# Sheet1.net
KiCad netlist of a schematic drawn in Altium Designer
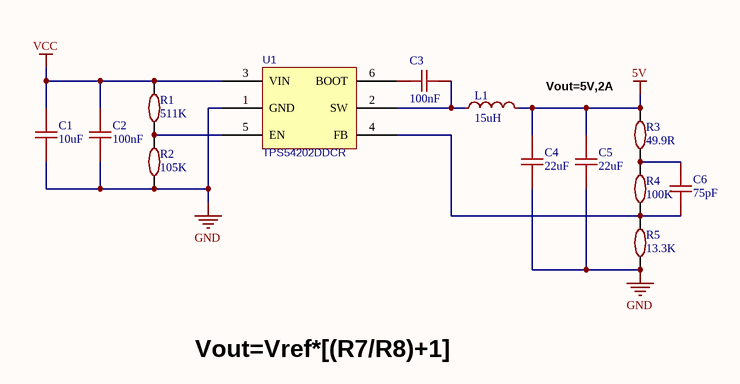
[diagram p0: Sheet1.SchDoc]

(export (version "E")
  (design (tool "Eeschema 10.0.6"))
  (components
    (comp (ref "C1")
      (value "10uF")
      (footprint "C_0603")
      (description "4.7nf-4.7uf")
      (libsource (lib "RCLD") (part "C_0603"))
    )
    (comp (ref "C2")
      (value "100nF")
      (footprint "C_0603")
      (description "4.7nf-4.7uf")
      (libsource (lib "RCLD") (part "C_0603"))
    )
    (comp (ref "C3")
      (value "100nF")
      (footprint "C_0603")
      (description "4.7nf-4.7uf")
      (libsource (lib "RCLD") (part "C_0603"))
    )
    (comp (ref "C4")
      (value "22uF")
      (footprint "C_0603")
      (description "4.7nf-4.7uf")
      (libsource (lib "RCLD") (part "C_0603"))
    )
    (comp (ref "C5")
      (value "22uF")
      (footprint "C_0603")
      (description "4.7nf-4.7uf")
      (libsource (lib "RCLD") (part "C_0603"))
    )
    (comp (ref "C6")
      (value "75pF")
      (footprint "C_0603")
      (description "4.7nf-4.7uf")
      (libsource (lib "RCLD") (part "C_0603"))
    )
    (comp (ref "L1")
      (value "15uH")
      (footprint "L-SMD-0630")
      (description "一体成型电感")
      (libsource (lib "RCLD") (part "L_33uH_0603"))
    )
    (comp (ref "R1") (value "511K") (footprint "R_0603") (libsource (lib "RCLD") (part "R_0603")))
    (comp (ref "R2") (value "105K") (footprint "R_0603") (libsource (lib "RCLD") (part "R_0603")))
    (comp (ref "R3") (value "49.9R") (footprint "R_0603") (libsource (lib "RCLD") (part "R_0603")))
    (comp (ref "R4") (value "100K") (footprint "R_0603") (libsource (lib "RCLD") (part "R_0603")))
    (comp (ref "R5") (value "13.3K") (footprint "R_0603") (libsource (lib "RCLD") (part "R_0603")))
    (comp (ref "U1")
      (value "TPS54202DDCR")
      (footprint "SOT23-6L")
      (fields (field (name "BOM_SUPPLIER PART") "C191884") (field (name "CONTRIBUTOR") "LCSC"))
      (libsource (lib "电源管理IC") (part "TPS54202DDCR"))
    )
  )
  (nets
    (net (code "1") (name "5V") (class "Default")
      (node (ref "C4") (pin "2") (pinfunction "2_2") (pintype "passive"))
      (node (ref "C5") (pin "2") (pinfunction "2_2") (pintype "passive"))
      (node (ref "L1") (pin "2") (pinfunction "2_2") (pintype "passive"))
      (node (ref "R3") (pin "2") (pinfunction "2_2") (pintype "passive"))
    )
    (net (code "2") (name "GND") (class "Default")
      (node (ref "C1") (pin "1") (pinfunction "1_1") (pintype "passive"))
      (node (ref "C2") (pin "1") (pinfunction "1_1") (pintype "passive"))
      (node (ref "C4") (pin "1") (pinfunction "1_1") (pintype "passive"))
      (node (ref "C5") (pin "1") (pinfunction "1_1") (pintype "passive"))
      (node (ref "R2") (pin "1") (pinfunction "1_1") (pintype "passive"))
      (node (ref "R5") (pin "1") (pinfunction "1_1") (pintype "passive"))
      (node (ref "U1") (pin "1") (pinfunction "GND_1") (pintype "passive"))
    )
    (net (code "3") (name "Net-(C6-Pad2)") (class "Default")
      (node (ref "C6") (pin "2") (pinfunction "2_2") (pintype "passive"))
      (node (ref "R3") (pin "1") (pinfunction "1_1") (pintype "passive"))
      (node (ref "R4") (pin "2") (pinfunction "2_2") (pintype "passive"))
    )
    (net (code "4") (name "Net-(U1-BOOT)") (class "Default")
      (node (ref "C3") (pin "2") (pinfunction "2_2") (pintype "passive"))
      (node (ref "U1") (pin "6") (pinfunction "BOOT_6") (pintype "passive"))
    )
    (net (code "5") (name "Net-(U1-EN)") (class "Default")
      (node (ref "R1") (pin "1") (pinfunction "1_1") (pintype "passive"))
      (node (ref "R2") (pin "2") (pinfunction "2_2") (pintype "passive"))
      (node (ref "U1") (pin "5") (pinfunction "EN_5") (pintype "passive"))
    )
    (net (code "6") (name "Net-(U1-FB)") (class "Default")
      (node (ref "C6") (pin "1") (pinfunction "1_1") (pintype "passive"))
      (node (ref "R4") (pin "1") (pinfunction "1_1") (pintype "passive"))
      (node (ref "R5") (pin "2") (pinfunction "2_2") (pintype "passive"))
      (node (ref "U1") (pin "4") (pinfunction "FB_4") (pintype "passive"))
    )
    (net (code "7") (name "Net-(U1-SW)") (class "Default")
      (node (ref "C3") (pin "1") (pinfunction "1_1") (pintype "passive"))
      (node (ref "L1") (pin "1") (pinfunction "1_1") (pintype "passive"))
      (node (ref "U1") (pin "2") (pinfunction "SW_2") (pintype "passive"))
    )
    (net (code "8") (name "VCC") (class "Default")
      (node (ref "C1") (pin "2") (pinfunction "2_2") (pintype "passive"))
      (node (ref "C2") (pin "2") (pinfunction "2_2") (pintype "passive"))
      (node (ref "R1") (pin "2") (pinfunction "2_2") (pintype "passive"))
      (node (ref "U1") (pin "3") (pinfunction "VIN_3") (pintype "passive"))
    )
  )
)
